# PDB_Core_v1_1_Sheet.net
KiCad netlist of a schematic drawn in Altium Designer
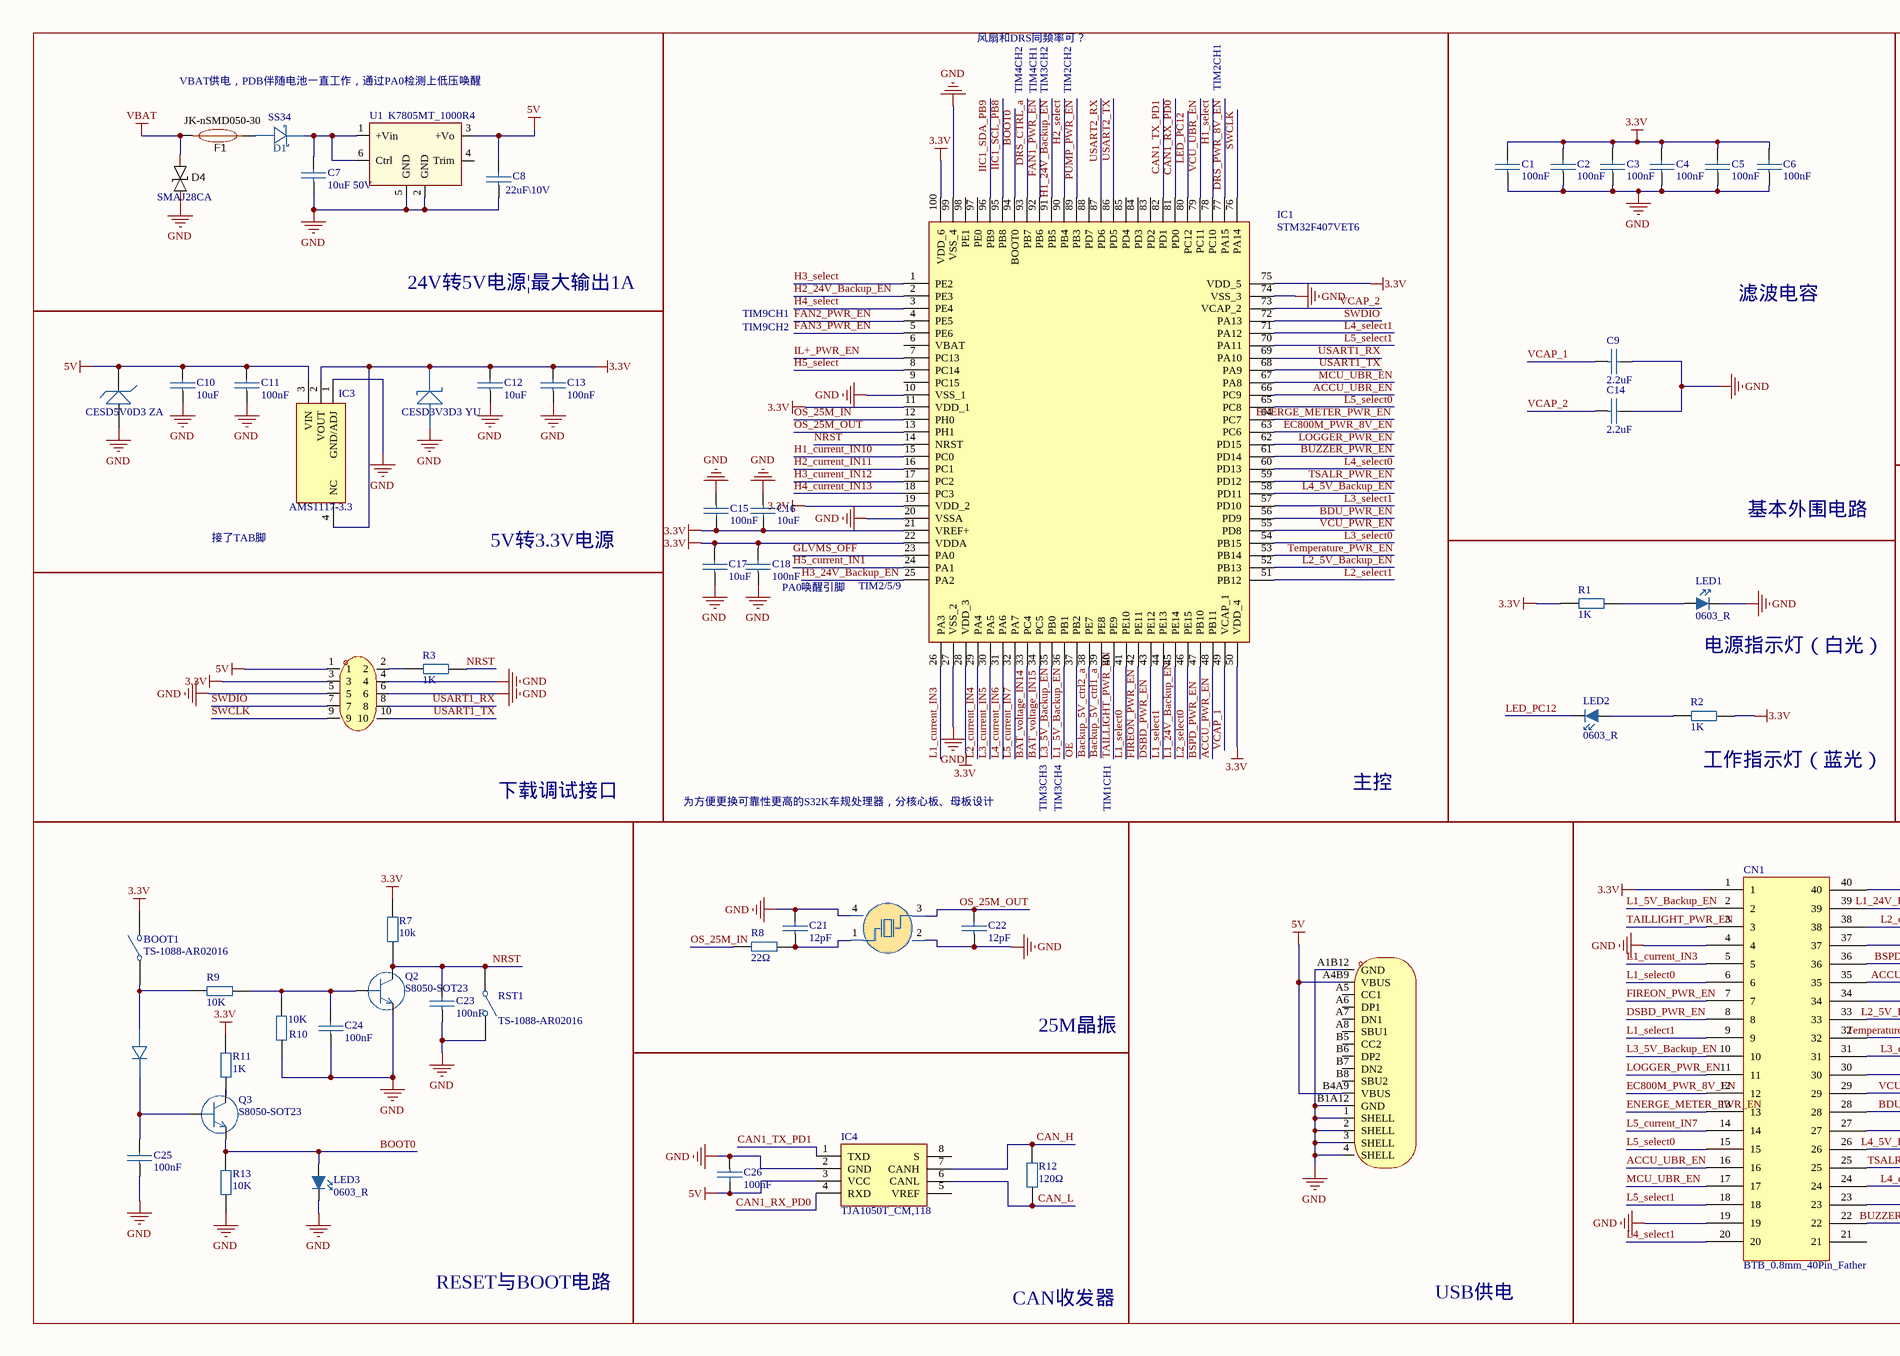
[diagram p0: PDB_Core_v1.1_Sheet.SchDoc, left]
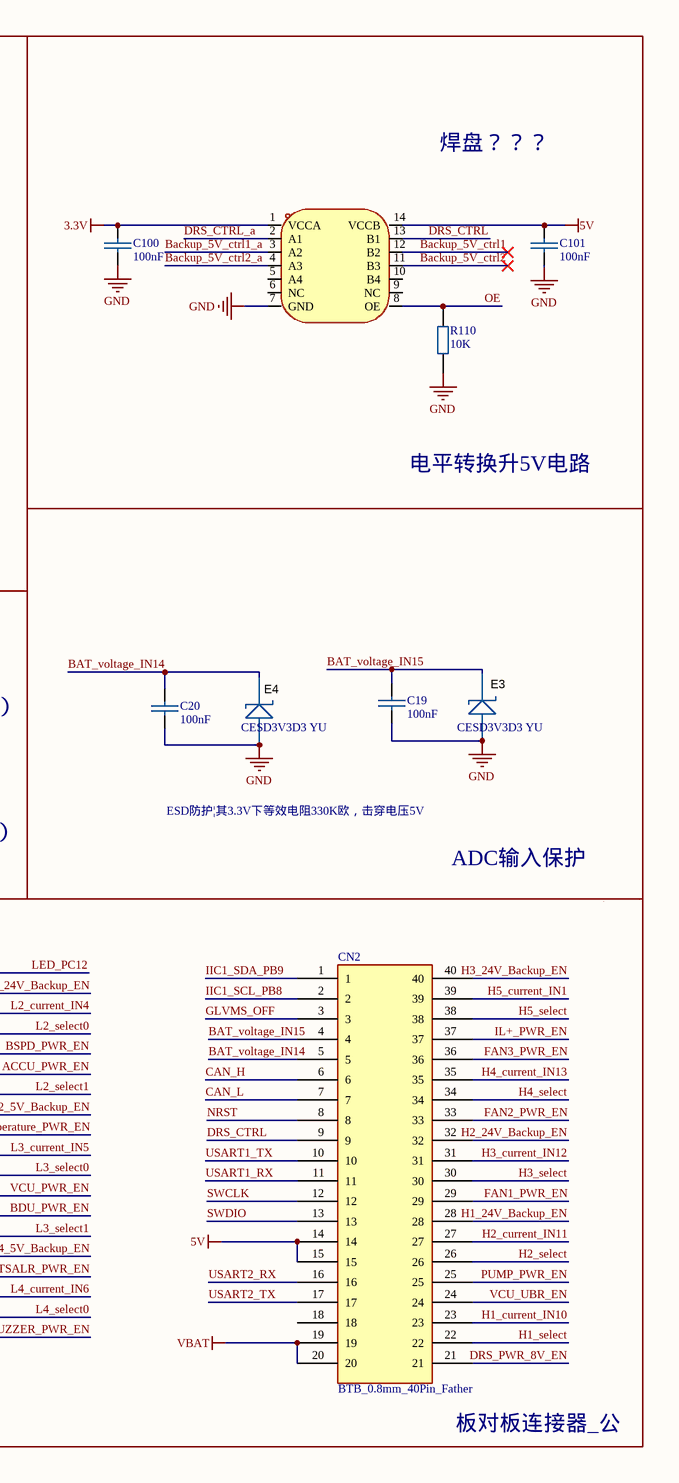
[diagram p1: PDB_Core_v1.1_Sheet.SchDoc, right]

(export (version "E")
  (design (tool "Eeschema 10.0.6"))
  (components
    (comp (ref "BOOT1")
      (value "TS-1088-AR02016")
      (footprint "SW-SMD_L3.9-W3.0-P4.45")
      (description "Switch")
      (libsource (lib "Switches") (part "TS-1088-AR02016"))
    )
    (comp (ref "C1")
      (value "100nF")
      (footprint "CAPC1608X08N__0603CAPUNPOLE")
      (description "Std MLCC Cap")
      (libsource (lib "ResistorCapacitorInductor") (part "SMD_MLCC"))
    )
    (comp (ref "C2")
      (value "100nF")
      (footprint "CAPC1608X08N__0603CAPUNPOLE")
      (description "Std MLCC Cap")
      (libsource (lib "ResistorCapacitorInductor") (part "SMD_MLCC"))
    )
    (comp (ref "C3")
      (value "100nF")
      (footprint "CAPC1608X08N__0603CAPUNPOLE")
      (description "Std MLCC Cap")
      (libsource (lib "ResistorCapacitorInductor") (part "SMD_MLCC"))
    )
    (comp (ref "C4")
      (value "100nF")
      (footprint "CAPC1608X08N__0603CAPUNPOLE")
      (description "Std MLCC Cap")
      (libsource (lib "ResistorCapacitorInductor") (part "SMD_MLCC"))
    )
    (comp (ref "C5")
      (value "100nF")
      (footprint "CAPC1608X08N__0603CAPUNPOLE")
      (description "Std MLCC Cap")
      (libsource (lib "ResistorCapacitorInductor") (part "SMD_MLCC"))
    )
    (comp (ref "C6")
      (value "100nF")
      (footprint "CAPC1608X08N__0603CAPUNPOLE")
      (description "Std MLCC Cap")
      (libsource (lib "ResistorCapacitorInductor") (part "SMD_MLCC"))
    )
    (comp (ref "C7")
      (value "10uF 50V")
      (footprint "CAPC3216X16N_1206CAPUNPOLE")
      (description "Std MLCC Cap")
      (libsource (lib "ResistorCapacitorInductor") (part "SMD_MLCC"))
    )
    (comp (ref "C8")
      (value "22u~{F}10V")
      (footprint "CAPC1608X08N__0603CAPUNPOLE")
      (description "Std MLCC Cap")
      (libsource (lib "ResistorCapacitorInductor") (part "SMD_MLCC"))
    )
    (comp (ref "C9")
      (value "2.2uF")
      (footprint "CAPC1608X08N__0603CAPUNPOLE")
      (description "Std MLCC Cap")
      (libsource (lib "ResistorCapacitorInductor") (part "SMD_MLCC"))
    )
    (comp (ref "C10")
      (value "10uF")
      (footprint "CAPC1608X08N__0603CAPUNPOLE")
      (description "Std MLCC Cap")
      (libsource (lib "ResistorCapacitorInductor") (part "SMD_MLCC"))
    )
    (comp (ref "C11")
      (value "100nF")
      (footprint "CAPC1608X08N__0603CAPUNPOLE")
      (description "Std MLCC Cap")
      (libsource (lib "ResistorCapacitorInductor") (part "SMD_MLCC"))
    )
    (comp (ref "C12")
      (value "10uF")
      (footprint "CAPC1608X08N__0603CAPUNPOLE")
      (description "Std MLCC Cap")
      (libsource (lib "ResistorCapacitorInductor") (part "SMD_MLCC"))
    )
    (comp (ref "C13")
      (value "100nF")
      (footprint "CAPC1608X08N__0603CAPUNPOLE")
      (description "Std MLCC Cap")
      (libsource (lib "ResistorCapacitorInductor") (part "SMD_MLCC"))
    )
    (comp (ref "C14")
      (value "2.2uF")
      (footprint "CAPC1608X08N__0603CAPUNPOLE")
      (description "Std MLCC Cap")
      (libsource (lib "ResistorCapacitorInductor") (part "SMD_MLCC"))
    )
    (comp (ref "C15")
      (value "100nF")
      (footprint "CAPC1608X08N__0603CAPUNPOLE")
      (description "Std MLCC Cap")
      (libsource (lib "ResistorCapacitorInductor") (part "SMD_MLCC"))
    )
    (comp (ref "C16")
      (value "10uF")
      (footprint "CAPC1608X08N__0603CAPUNPOLE")
      (description "Std MLCC Cap")
      (libsource (lib "ResistorCapacitorInductor") (part "SMD_MLCC"))
    )
    (comp (ref "C17")
      (value "10uF")
      (footprint "CAPC1608X08N__0603CAPUNPOLE")
      (description "Std MLCC Cap")
      (libsource (lib "ResistorCapacitorInductor") (part "SMD_MLCC"))
    )
    (comp (ref "C18")
      (value "100nF")
      (footprint "CAPC1608X08N__0603CAPUNPOLE")
      (description "Std MLCC Cap")
      (libsource (lib "ResistorCapacitorInductor") (part "SMD_MLCC"))
    )
    (comp (ref "C19")
      (value "100nF")
      (footprint "CAPC1608X08N__0603CAPUNPOLE")
      (description "Std MLCC Cap")
      (libsource (lib "ResistorCapacitorInductor") (part "SMD_MLCC"))
    )
    (comp (ref "C20")
      (value "100nF")
      (footprint "CAPC1608X08N__0603CAPUNPOLE")
      (description "Std MLCC Cap")
      (libsource (lib "ResistorCapacitorInductor") (part "SMD_MLCC"))
    )
    (comp (ref "C21")
      (value "12pF")
      (footprint "CAPC1608X08N__0603CAPUNPOLE")
      (description "Std MLCC Cap")
      (libsource (lib "ResistorCapacitorInductor") (part "SMD_MLCC"))
    )
    (comp (ref "C22")
      (value "12pF")
      (footprint "CAPC1608X08N__0603CAPUNPOLE")
      (description "Std MLCC Cap")
      (libsource (lib "ResistorCapacitorInductor") (part "SMD_MLCC"))
    )
    (comp (ref "C23")
      (value "100nF")
      (footprint "CAPC1608X08N__0603CAPUNPOLE")
      (description "Std MLCC Cap")
      (libsource (lib "ResistorCapacitorInductor") (part "SMD_MLCC"))
    )
    (comp (ref "C24")
      (value "100nF")
      (footprint "CAPC1608X08N__0603CAPUNPOLE")
      (description "Std MLCC Cap")
      (libsource (lib "ResistorCapacitorInductor") (part "SMD_MLCC"))
    )
    (comp (ref "C25")
      (value "100nF")
      (footprint "CAPC1608X08N__0603CAPUNPOLE")
      (description "Std MLCC Cap")
      (libsource (lib "ResistorCapacitorInductor") (part "SMD_MLCC"))
    )
    (comp (ref "C26")
      (value "100nF")
      (footprint "CAPC1608X08N__0603CAPUNPOLE")
      (description "Std MLCC Cap")
      (libsource (lib "ResistorCapacitorInductor") (part "SMD_MLCC"))
    )
    (comp (ref "C100")
      (value "100nF")
      (footprint "CAPC1608X08N__0603CAPUNPOLE")
      (description "Std MLCC Cap")
      (libsource (lib "ResistorCapacitorInductor") (part "SMD_MLCC"))
    )
    (comp (ref "C101")
      (value "100nF")
      (footprint "CAPC1608X08N__0603CAPUNPOLE")
      (description "Std MLCC Cap")
      (libsource (lib "ResistorCapacitorInductor") (part "SMD_MLCC"))
    )
    (comp (ref "CN1")
      (value "BTB_0.8mm_40Pin_Father")
      (footprint "BTB_0.8mm_40PIN_F")
      (libsource (lib "Connector") (part "BTB_0.8mm_40Pin_Father"))
    )
    (comp (ref "CN2")
      (value "BTB_0.8mm_40Pin_Father")
      (footprint "BTB_0.8mm_40PIN_F")
      (libsource (lib "Connector") (part "BTB_0.8mm_40Pin_Father"))
    )
    (comp (ref "D1")
      (value "SS34")
      (footprint "SMA_L4.3-W2.6-LS5.2-RD")
      (description "二极管配置:独立式;直流反向耐压(Vr):40V;平均整流电流(Io):3A;正向压降(Vf):550mV@3A; C8678")
      (fields (field (name "MANUFACTURER") "MDD"))
      (libsource (lib "Diodes") (part "SS34_C8678"))
    )
    (comp (ref "D3")
      (value "1N4148WS_C2128")
      (footprint "SOD-323_L1.8-W1.3-LS2.5-RD")
      (fields (field (name "MANUFACTURER") "CJ(江苏长电/长晶)") (field (name "MANUFACTURER PART") "1N4148WS"))
      (libsource (lib "Diodes") (part "1N4148WS_C2128"))
    )
    (comp (ref "D4")
      (value "SMAJ28CA")
      (footprint "SMA_L4.3-W2.5-LS5.0-BI")
      (description "C353457")
      (fields (field (name "MANUFACTURER") "晶导微电子"))
      (libsource (lib "Diodes") (part "SMAJ28CA_C353457"))
    )
    (comp (ref "E1")
      (value "CESD5V0D3 ZA")
      (footprint "SOD-323_L1.8-W1.3-LS2.5-RD")
      (fields (field (name "MANUFACTURER") "CJ(江苏长电/长晶)"))
      (libsource (lib "Diodes") (part "CESD5V0D3 ZA"))
    )
    (comp (ref "E2")
      (value "CESD3V3D3 YU")
      (footprint "SOD-323_L1.8-W1.3-LS2.5-RD")
      (description "极性:单向;反向截止电压(Vrwm):3.3V;击穿电压(VBR):5V;钳位电压(Vc)@Ipp:13V;")
      (fields (field (name "MANUFACTURER") "CJ(江苏长电/长晶)"))
      (libsource (lib "Diodes") (part "CESD3V3D3 YU"))
    )
    (comp (ref "E3")
      (value "CESD3V3D3 YU")
      (footprint "SOD-323_L1.8-W1.3-LS2.5-RD")
      (description "极性:单向;反向截止电压(Vrwm):3.3V;击穿电压(VBR):5V;钳位电压(Vc)@Ipp:13V;")
      (fields (field (name "MANUFACTURER") "CJ(江苏长电/长晶)"))
      (libsource (lib "Diodes") (part "CESD3V3D3 YU"))
    )
    (comp (ref "E4")
      (value "CESD3V3D3 YU")
      (footprint "SOD-323_L1.8-W1.3-LS2.5-RD")
      (description "极性:单向;反向截止电压(Vrwm):3.3V;击穿电压(VBR):5V;钳位电压(Vc)@Ipp:13V;")
      (fields (field (name "MANUFACTURER") "CJ(江苏长电/长晶)"))
      (libsource (lib "Diodes") (part "CESD3V3D3 YU"))
    )
    (comp (ref "F1")
      (value "JK-nSMD050-30")
      (footprint "F1206")
      (description "C720075")
      (fields (field (name "MANUFACTURER") "JK(金科)"))
      (libsource (lib "Fuse") (part "JK-nSMD050-30"))
    )
    (comp (ref "IC1")
      (value "STM32F407VET6")
      (footprint "QFP50P1600X1600X160-100N")
      (description "Integrated Circuit")
      (fields (field (name "MOUSER PART NUMBER") "511-STM32F407VET6"))
      (libsource (lib "*") (part "STM32F407VET6"))
    )
    (comp (ref "IC3")
      (value "AMS1117-3.3")
      (footprint "SOT229P700X180-4N")
      (description "Integrated Circuit")
      (libsource (lib "*") (part "AMS1117-3.3"))
    )
    (comp (ref "IC4")
      (value "TJA1050T_CM,118")
      (footprint "SOIC127P600X175-8N")
      (description "Integrated Circuit")
      (fields
        (field (name "MANUFACTURER_PART_NUMBER") "TJA1050T/CM,118")
        (field (name "MOUSER PART NUMBER") "771-TJA1050T/CM118")
      )
      (libsource (lib "*") (part "TJA1050T_CM,118"))
    )
    (comp (ref "LED1")
      (value "0603_R")
      (footprint "LED0603-RD_RED")
      (description "Light Emitting Diode")
      (libsource (lib "Diodes") (part "LED"))
    )
    (comp (ref "LED2")
      (value "0603_R")
      (footprint "LED0603-RD_RED")
      (description "Light Emitting Diode")
      (libsource (lib "Diodes") (part "LED"))
    )
    (comp (ref "LED3")
      (value "0603_R")
      (footprint "LED0603-RD_RED")
      (description "Light Emitting Diode")
      (libsource (lib "Diodes") (part "LED"))
    )
    (comp (ref "Q2")
      (value "S8050-SOT23")
      (footprint "SOT95P245X110-3N")
      (description "Jellybeam NPN")
      (libsource (lib "Transistor") (part "S8050"))
    )
    (comp (ref "Q3")
      (value "S8050-SOT23")
      (footprint "SOT95P245X110-3N")
      (description "Jellybeam NPN")
      (libsource (lib "Transistor") (part "S8050"))
    )
    (comp (ref "R1")
      (value "1K")
      (footprint "RESC1608X04N_0603RES")
      (description "Std Resistor")
      (libsource (lib "ResistorCapacitorInductor") (part "SMD_Resistor"))
    )
    (comp (ref "R2")
      (value "1K")
      (footprint "RESC1608X04N_0603RES")
      (description "Std Resistor")
      (libsource (lib "ResistorCapacitorInductor") (part "SMD_Resistor"))
    )
    (comp (ref "R3")
      (value "1K")
      (footprint "RESC3116X06N__1206RES")
      (description "Std Resistor")
      (libsource (lib "ResistorCapacitorInductor") (part "SMD_Resistor"))
    )
    (comp (ref "R7")
      (value "10k")
      (footprint "RESC1608X04N_0603RES")
      (description "Std Resistor")
      (libsource (lib "ResistorCapacitorInductor") (part "SMD_Resistor"))
    )
    (comp (ref "R8")
      (value "22Ω")
      (footprint "RESC1608X04N_0603RES")
      (description "Std Resistor")
      (libsource (lib "ResistorCapacitorInductor") (part "SMD_Resistor"))
    )
    (comp (ref "R9")
      (value "10K")
      (footprint "RESC1608X04N_0603RES")
      (description "Std Resistor")
      (libsource (lib "ResistorCapacitorInductor") (part "SMD_Resistor"))
    )
    (comp (ref "R10")
      (value "10K")
      (footprint "RESC1608X04N_0603RES")
      (description "Std Resistor")
      (libsource (lib "ResistorCapacitorInductor") (part "SMD_Resistor"))
    )
    (comp (ref "R11")
      (value "1K")
      (footprint "RESC1608X04N_0603RES")
      (description "Std Resistor")
      (libsource (lib "ResistorCapacitorInductor") (part "SMD_Resistor"))
    )
    (comp (ref "R12")
      (value "120Ω")
      (footprint "RESC1608X04N_0603RES")
      (description "Std Resistor")
      (libsource (lib "ResistorCapacitorInductor") (part "SMD_Resistor"))
    )
    (comp (ref "R13")
      (value "10K")
      (footprint "RESC1608X04N_0603RES")
      (description "Std Resistor")
      (libsource (lib "ResistorCapacitorInductor") (part "SMD_Resistor"))
    )
    (comp (ref "R110")
      (value "10K")
      (footprint "RESC1608X04N_0603RES")
      (description "Std Resistor")
      (libsource (lib "ResistorCapacitorInductor") (part "SMD_Resistor"))
    )
    (comp (ref "RST1")
      (value "TS-1088-AR02016")
      (footprint "SW-SMD_L3.9-W3.0-P4.45")
      (description "Switch")
      (libsource (lib "Switches") (part "TS-1088-AR02016"))
    )
    (comp (ref "U1")
      (value "K7805MT_1000R4")
      (footprint "K7805MT_500R4")
      (libsource (lib "DCDC_Converter") (part "K78052MT_1000R4"))
    )
    (comp (ref "U2")
      (value "ZX-PZ2.54-2-5PZZ")
      (footprint "HDR-TH_10P-P2.54-V-M-R2-C5-S2.54")
      (fields (field (name "MANUFACTURER") "Megastar(兆星)"))
      (libsource (lib "Connector") (part "ZX-PZ2.54-2-5PZZ"))
    )
    (comp (ref "U3")
      (value "TXS0104EPWR")
      (footprint "TSSOP-14_L5.0-W4.4-P0.65-LS6.4-BL")
      (description "C44955 电平转换芯片")
      (fields (field (name "MANUFACTURER") "TI(德州仪器)"))
      (libsource (lib "GateDrivers") (part "TXS0104EPWR"))
    )
    (comp (ref "USB1")
      (value "TYPE-C16PIN")
      (footprint "USB-C-SMD_TYPE-C16PIN")
      (description "C393939")
      (fields (field (name "MANUFACTURER") "SHOU HAN(首韩)"))
      (libsource (lib "Connector") (part "TYPE-C16PIN"))
    )
    (comp (ref "X1")
      (value "X322525MOB4SI")
      (footprint "OSC-SMD_4P-L3.2-W2.5-BL")
      (description "频率:25MHz;频率公差:±10ppm;负载电容:12pF;")
      (fields (field (name "MANUFACTURER") "YXC(扬兴晶振)"))
      (libsource (lib "Crystals") (part "X322525MOB4SI"))
    )
  )
  (nets
    (net (code "1") (name "/ACCU_PWR_EN") (class "Default")
      (node (ref "CN1") (pin "35") (pinfunction "35_35") (pintype "passive"))
      (node (ref "IC1") (pin "48") (pinfunction "PB11_48") (pintype "passive"))
    )
    (net (code "2") (name "/ACCU_UBR_EN") (class "Default")
      (node (ref "CN1") (pin "16") (pinfunction "16_16") (pintype "passive"))
      (node (ref "IC1") (pin "66") (pinfunction "PC9_66") (pintype "passive"))
    )
    (net (code "3") (name "/BAT_voltage_IN14") (class "Default")
      (node (ref "C20") (pin "2") (pintype "passive"))
      (node (ref "CN2") (pin "5") (pinfunction "5_5") (pintype "passive"))
      (node (ref "E4") (pin "1") (pinfunction "1_1") (pintype "passive"))
      (node (ref "IC1") (pin "33") (pinfunction "PC4_33") (pintype "passive"))
    )
    (net (code "4") (name "/BAT_voltage_IN15") (class "Default")
      (node (ref "C19") (pin "2") (pintype "passive"))
      (node (ref "CN2") (pin "4") (pinfunction "4_4") (pintype "passive"))
      (node (ref "E3") (pin "1") (pinfunction "1_1") (pintype "passive"))
      (node (ref "IC1") (pin "34") (pinfunction "PC5_34") (pintype "passive"))
    )
    (net (code "5") (name "/BDU_PWR_EN") (class "Default")
      (node (ref "CN1") (pin "28") (pinfunction "28_28") (pintype "passive"))
      (node (ref "IC1") (pin "56") (pinfunction "PD9_56") (pintype "passive"))
    )
    (net (code "6") (name "/BOOT0") (class "Default")
      (node (ref "IC1") (pin "94") (pinfunction "BOOT0_94") (pintype "passive"))
      (node (ref "LED3") (pin "2") (pintype "passive"))
      (node (ref "Q3") (pin "2") (pinfunction "Emitter_2") (pintype "passive"))
      (node (ref "R13") (pin "2") (pintype "passive"))
    )
    (net (code "7") (name "/BSPD_PWR_EN") (class "Default")
      (node (ref "CN1") (pin "36") (pinfunction "36_36") (pintype "passive"))
      (node (ref "IC1") (pin "47") (pinfunction "PB10_47") (pintype "passive"))
    )
    (net (code "8") (name "/BUZZER_PWR_EN") (class "Default")
      (node (ref "CN1") (pin "22") (pinfunction "22_22") (pintype "passive"))
      (node (ref "IC1") (pin "61") (pinfunction "PD14_61") (pintype "passive"))
    )
    (net (code "9") (name "/Backup_5V_ctrl1") (class "Default")
      (node (ref "U3") (pin "12") (pinfunction "B2_12") (pintype "passive+no_connect"))
    )
    (net (code "10") (name "/Backup_5V_ctrl1_a") (class "Default")
      (node (ref "IC1") (pin "39") (pinfunction "PE8_39") (pintype "passive"))
      (node (ref "U3") (pin "3") (pinfunction "A2_3") (pintype "passive"))
    )
    (net (code "11") (name "/Backup_5V_ctrl2") (class "Default")
      (node (ref "U3") (pin "11") (pinfunction "B3_11") (pintype "passive+no_connect"))
    )
    (net (code "12") (name "/Backup_5V_ctrl2_a") (class "Default")
      (node (ref "IC1") (pin "38") (pinfunction "PE7_38") (pintype "passive"))
      (node (ref "U3") (pin "4") (pinfunction "A3_4") (pintype "passive"))
    )
    (net (code "13") (name "/CAN1_RX_PD0") (class "Default")
      (node (ref "IC1") (pin "81") (pinfunction "PD0_81") (pintype "passive"))
      (node (ref "IC4") (pin "4") (pinfunction "RXD_4") (pintype "passive"))
    )
    (net (code "14") (name "/CAN1_TX_PD1") (class "Default")
      (node (ref "IC1") (pin "82") (pinfunction "PD1_82") (pintype "passive"))
      (node (ref "IC4") (pin "1") (pinfunction "TXD_1") (pintype "passive"))
    )
    (net (code "15") (name "/CAN_H") (class "Default")
      (node (ref "CN2") (pin "6") (pinfunction "6_6") (pintype "passive"))
      (node (ref "IC4") (pin "7") (pinfunction "CANH_7") (pintype "passive"))
      (node (ref "R12") (pin "2") (pintype "passive"))
    )
    (net (code "16") (name "/CAN_L") (class "Default")
      (node (ref "CN2") (pin "7") (pinfunction "7_7") (pintype "passive"))
      (node (ref "IC4") (pin "6") (pinfunction "CANL_6") (pintype "passive"))
      (node (ref "R12") (pin "1") (pintype "passive"))
    )
    (net (code "17") (name "/DRS_CTRL") (class "Default")
      (node (ref "CN2") (pin "9") (pinfunction "9_9") (pintype "passive"))
      (node (ref "U3") (pin "13") (pinfunction "B1_13") (pintype "passive"))
    )
    (net (code "18") (name "/DRS_CTRL_a") (class "Default")
      (node (ref "IC1") (pin "93") (pinfunction "PB7_93") (pintype "passive"))
      (node (ref "U3") (pin "2") (pinfunction "A1_2") (pintype "passive"))
    )
    (net (code "19") (name "/DRS_PWR_8V_EN") (class "Default")
      (node (ref "CN2") (pin "21") (pinfunction "21_21") (pintype "passive"))
      (node (ref "IC1") (pin "77") (pinfunction "PA15_77") (pintype "passive"))
    )
    (net (code "20") (name "/DSBD_PWR_EN") (class "Default")
      (node (ref "CN1") (pin "8") (pinfunction "8_8") (pintype "passive"))
      (node (ref "IC1") (pin "43") (pinfunction "PE12_43") (pintype "passive"))
    )
    (net (code "21") (name "/EC800M_PWR_8V_EN") (class "Default")
      (node (ref "CN1") (pin "12") (pinfunction "12_12") (pintype "passive"))
      (node (ref "IC1") (pin "63") (pinfunction "PC6_63") (pintype "passive"))
    )
    (net (code "22") (name "/ENERGE_METER_PWR_EN") (class "Default")
      (node (ref "CN1") (pin "13") (pinfunction "13_13") (pintype "passive"))
      (node (ref "IC1") (pin "64") (pinfunction "PC7_64") (pintype "passive"))
    )
    (net (code "23") (name "/FAN1_PWR_EN") (class "Default")
      (node (ref "CN2") (pin "29") (pinfunction "29_29") (pintype "passive"))
      (node (ref "IC1") (pin "92") (pinfunction "PB6_92") (pintype "passive"))
    )
    (net (code "24") (name "/FAN2_PWR_EN") (class "Default")
      (node (ref "CN2") (pin "33") (pinfunction "33_33") (pintype "passive"))
      (node (ref "IC1") (pin "4") (pinfunction "PE5_4") (pintype "passive"))
    )
    (net (code "25") (name "/FAN3_PWR_EN") (class "Default")
      (node (ref "CN2") (pin "36") (pinfunction "36_36") (pintype "passive"))
      (node (ref "IC1") (pin "5") (pinfunction "PE6_5") (pintype "passive"))
    )
    (net (code "26") (name "/FIREON_PWR_EN") (class "Default")
      (node (ref "CN1") (pin "7") (pinfunction "7_7") (pintype "passive"))
      (node (ref "IC1") (pin "42") (pinfunction "PE11_42") (pintype "passive"))
    )
    (net (code "27") (name "/GLVMS_OFF") (class "Default")
      (node (ref "CN2") (pin "3") (pinfunction "3_3") (pintype "passive"))
      (node (ref "IC1") (pin "23") (pinfunction "PA0_23") (pintype "passive"))
    )
    (net (code "28") (name "/H1_24V_Backup_EN") (class "Default")
      (node (ref "CN2") (pin "28") (pinfunction "28_28") (pintype "passive"))
      (node (ref "IC1") (pin "91") (pinfunction "PB5_91") (pintype "passive"))
    )
    (net (code "29") (name "/H1_current_IN10") (class "Default")
      (node (ref "CN2") (pin "23") (pinfunction "23_23") (pintype "passive"))
      (node (ref "IC1") (pin "15") (pinfunction "PC0_15") (pintype "passive"))
    )
    (net (code "30") (name "/H1_select") (class "Default")
      (node (ref "CN2") (pin "22") (pinfunction "22_22") (pintype "passive"))
      (node (ref "IC1") (pin "78") (pinfunction "PC10_78") (pintype "passive"))
    )
    (net (code "31") (name "/H2_24V_Backup_EN") (class "Default")
      (node (ref "CN2") (pin "32") (pinfunction "32_32") (pintype "passive"))
      (node (ref "IC1") (pin "2") (pinfunction "PE3_2") (pintype "passive"))
    )
    (net (code "32") (name "/H2_current_IN11") (class "Default")
      (node (ref "CN2") (pin "27") (pinfunction "27_27") (pintype "passive"))
      (node (ref "IC1") (pin "16") (pinfunction "PC1_16") (pintype "passive"))
    )
    (net (code "33") (name "/H2_select") (class "Default")
      (node (ref "CN2") (pin "26") (pinfunction "26_26") (pintype "passive"))
      (node (ref "IC1") (pin "90") (pinfunction "PB4_90") (pintype "passive"))
    )
    (net (code "34") (name "/H3_24V_Backup_EN") (class "Default")
      (node (ref "CN2") (pin "40") (pinfunction "40_40") (pintype "passive"))
      (node (ref "IC1") (pin "25") (pinfunction "PA2_25") (pintype "passive"))
    )
    (net (code "35") (name "/H3_current_IN12") (class "Default")
      (node (ref "CN2") (pin "31") (pinfunction "31_31") (pintype "passive"))
      (node (ref "IC1") (pin "17") (pinfunction "PC2_17") (pintype "passive"))
    )
    (net (code "36") (name "/H3_select") (class "Default")
      (node (ref "CN2") (pin "30") (pinfunction "30_30") (pintype "passive"))
      (node (ref "IC1") (pin "1") (pinfunction "PE2_1") (pintype "passive"))
    )
    (net (code "37") (name "/H4_current_IN13") (class "Default")
      (node (ref "CN2") (pin "35") (pinfunction "35_35") (pintype "passive"))
      (node (ref "IC1") (pin "18") (pinfunction "PC3_18") (pintype "passive"))
    )
    (net (code "38") (name "/H4_select") (class "Default")
      (node (ref "CN2") (pin "34") (pinfunction "34_34") (pintype "passive"))
      (node (ref "IC1") (pin "3") (pinfunction "PE4_3") (pintype "passive"))
    )
    (net (code "39") (name "/H5_current_IN1") (class "Default")
      (node (ref "CN2") (pin "39") (pinfunction "39_39") (pintype "passive"))
      (node (ref "IC1") (pin "24") (pinfunction "PA1_24") (pintype "passive"))
    )
    (net (code "40") (name "/H5_select") (class "Default")
      (node (ref "CN2") (pin "38") (pinfunction "38_38") (pintype "passive"))
      (node (ref "IC1") (pin "8") (pinfunction "PC14_8") (pintype "passive"))
    )
    (net (code "41") (name "/IIC1_SCL_PB8") (class "Default")
      (node (ref "CN2") (pin "2") (pinfunction "2_2") (pintype "passive"))
      (node (ref "IC1") (pin "95") (pinfunction "PB8_95") (pintype "passive"))
    )
    (net (code "42") (name "/IIC1_SDA_PB9") (class "Default")
      (node (ref "CN2") (pin "1") (pinfunction "1_1") (pintype "passive"))
      (node (ref "IC1") (pin "96") (pinfunction "PB9_96") (pintype "passive"))
    )
    (net (code "43") (name "/IL+_PWR_EN") (class "Default")
      (node (ref "CN2") (pin "37") (pinfunction "37_37") (pintype "passive"))
      (node (ref "IC1") (pin "7") (pinfunction "PC13_7") (pintype "passive"))
    )
    (net (code "44") (name "/L1_5V_Backup_EN") (class "Default")
      (node (ref "CN1") (pin "2") (pinfunction "2_2") (pintype "passive"))
      (node (ref "IC1") (pin "36") (pinfunction "PB1_36") (pintype "passive"))
    )
    (net (code "45") (name "/L1_24V_Backup_EN") (class "Default")
      (node (ref "CN1") (pin "39") (pinfunction "39_39") (pintype "passive"))
      (node (ref "IC1") (pin "45") (pinfunction "PE14_45") (pintype "passive"))
    )
    (net (code "46") (name "/L1_current_IN3") (class "Default")
      (node (ref "CN1") (pin "5") (pinfunction "5_5") (pintype "passive"))
      (node (ref "IC1") (pin "26") (pinfunction "PA3_26") (pintype "passive"))
    )
    (net (code "47") (name "/L1_select0") (class "Default")
      (node (ref "CN1") (pin "6") (pinfunction "6_6") (pintype "passive"))
      (node (ref "IC1") (pin "41") (pinfunction "PE10_41") (pintype "passive"))
    )
    (net (code "48") (name "/L1_select1") (class "Default")
      (node (ref "CN1") (pin "9") (pinfunction "9_9") (pintype "passive"))
      (node (ref "IC1") (pin "44") (pinfunction "PE13_44") (pintype "passive"))
    )
    (net (code "49") (name "/L2_5V_Backup_EN") (class "Default")
      (node (ref "CN1") (pin "33") (pinfunction "33_33") (pintype "passive"))
      (node (ref "IC1") (pin "52") (pinfunction "PB13_52") (pintype "passive"))
    )
    (net (code "50") (name "/L2_current_IN4") (class "Default")
      (node (ref "CN1") (pin "38") (pinfunction "38_38") (pintype "passive"))
      (node (ref "IC1") (pin "29") (pinfunction "PA4_29") (pintype "passive"))
    )
    (net (code "51") (name "/L2_select0") (class "Default")
      (node (ref "CN1") (pin "37") (pinfunction "37_37") (pintype "passive"))
      (node (ref "IC1") (pin "46") (pinfunction "PE15_46") (pintype "passive"))
    )
    (net (code "52") (name "/L2_select1") (class "Default")
      (node (ref "CN1") (pin "34") (pinfunction "34_34") (pintype "passive"))
      (node (ref "IC1") (pin "51") (pinfunction "PB12_51") (pintype "passive"))
    )
    (net (code "53") (name "/L3_5V_Backup_EN") (class "Default")
      (node (ref "CN1") (pin "10") (pinfunction "10_10") (pintype "passive"))
      (node (ref "IC1") (pin "35") (pinfunction "PB0_35") (pintype "passive"))
    )
    (net (code "54") (name "/L3_current_IN5") (class "Default")
      (node (ref "CN1") (pin "31") (pinfunction "31_31") (pintype "passive"))
      (node (ref "IC1") (pin "30") (pinfunction "PA5_30") (pintype "passive"))
    )
    (net (code "55") (name "/L3_select0") (class "Default")
      (node (ref "CN1") (pin "30") (pinfunction "30_30") (pintype "passive"))
      (node (ref "IC1") (pin "54") (pinfunction "PB15_54") (pintype "passive"))
    )
    (net (code "56") (name "/L3_select1") (class "Default")
      (node (ref "CN1") (pin "27") (pinfunction "27_27") (pintype "passive"))
      (node (ref "IC1") (pin "57") (pinfunction "PD10_57") (pintype "passive"))
    )
    (net (code "57") (name "/L4_5V_Backup_EN") (class "Default")
      (node (ref "CN1") (pin "26") (pinfunction "26_26") (pintype "passive"))
      (node (ref "IC1") (pin "58") (pinfunction "PD11_58") (pintype "passive"))
    )
    (net (code "58") (name "/L4_current_IN6") (class "Default")
      (node (ref "CN1") (pin "24") (pinfunction "24_24") (pintype "passive"))
      (node (ref "IC1") (pin "31") (pinfunction "PA6_31") (pintype "passive"))
    )
    (net (code "59") (name "/L4_select0") (class "Default")
      (node (ref "CN1") (pin "23") (pinfunction "23_23") (pintype "passive"))
      (node (ref "IC1") (pin "60") (pinfunction "PD13_60") (pintype "passive"))
    )
    (net (code "60") (name "/L4_select1") (class "Default")
      (node (ref "CN1") (pin "20") (pinfunction "20_20") (pintype "passive"))
      (node (ref "IC1") (pin "71") (pinfunction "PA12_71") (pintype "passive"))
    )
    (net (code "61") (name "/L5_current_IN7") (class "Default")
      (node (ref "CN1") (pin "14") (pinfunction "14_14") (pintype "passive"))
      (node (ref "IC1") (pin "32") (pinfunction "PA7_32") (pintype "passive"))
    )
    (net (code "62") (name "/L5_select0") (class "Default")
      (node (ref "CN1") (pin "15") (pinfunction "15_15") (pintype "passive"))
      (node (ref "IC1") (pin "65") (pinfunction "PC8_65") (pintype "passive"))
    )
    (net (code "63") (name "/L5_select1") (class "Default")
      (node (ref "CN1") (pin "18") (pinfunction "18_18") (pintype "passive"))
      (node (ref "IC1") (pin "70") (pinfunction "PA11_70") (pintype "passive"))
    )
    (net (code "64") (name "/LED_PC12") (class "Default")
      (node (ref "CN1") (pin "40") (pinfunction "40_40") (pintype "passive"))
      (node (ref "IC1") (pin "80") (pinfunction "PC12_80") (pintype "passive"))
      (node (ref "LED2") (pin "1") (pintype "passive"))
    )
    (net (code "65") (name "/LOGGER_PWR_EN") (class "Default")
      (node (ref "CN1") (pin "11") (pinfunction "11_11") (pintype "passive"))
      (node (ref "IC1") (pin "62") (pinfunction "PD15_62") (pintype "passive"))
    )
    (net (code "66") (name "/MCU_UBR_EN") (class "Default")
      (node (ref "CN1") (pin "17") (pinfunction "17_17") (pintype "passive"))
      (node (ref "IC1") (pin "67") (pinfunction "PA8_67") (pintype "passive"))
    )
    (net (code "67") (name "/NRST") (class "Default")
      (node (ref "C23") (pin "2") (pintype "passive"))
      (node (ref "CN2") (pin "8") (pinfunction "8_8") (pintype "passive"))
      (node (ref "IC1") (pin "14") (pinfunction "NRST_14") (pintype "passive"))
      (node (ref "Q2") (pin "3") (pinfunction "Collector_3") (pintype "passive"))
      (node (ref "R3") (pin "2") (pintype "passive"))
      (node (ref "R7") (pin "1") (pintype "passive"))
      (node (ref "RST1") (pin "1") (pinfunction "COMMON_1") (pintype "passive"))
    )
    (net (code "68") (name "/OE") (class "Default")
      (node (ref "IC1") (pin "37") (pinfunction "PB2_37") (pintype "passive"))
      (node (ref "R110") (pin "2") (pintype "passive"))
      (node (ref "U3") (pin "8") (pinfunction "OE_8") (pintype "passive"))
    )
    (net (code "69") (name "/OS_25M_IN") (class "Default")
      (node (ref "IC1") (pin "12") (pinfunction "PH0_12") (pintype "passive"))
      (node (ref "R8") (pin "1") (pintype "passive"))
    )
    (net (code "70") (name "/OS_25M_OUT") (class "Default")
      (node (ref "C22") (pin "2") (pintype "passive"))
      (node (ref "IC1") (pin "13") (pinfunction "PH1_13") (pintype "passive"))
      (node (ref "X1") (pin "3") (pinfunction "OSC2_3") (pintype "passive"))
    )
    (net (code "71") (name "/PUMP_PWR_EN") (class "Default")
      (node (ref "CN2") (pin "25") (pinfunction "25_25") (pintype "passive"))
      (node (ref "IC1") (pin "89") (pinfunction "PB3_89") (pintype "passive"))
    )
    (net (code "72") (name "/SWCLK") (class "Default")
      (node (ref "CN2") (pin "12") (pinfunction "12_12") (pintype "passive"))
      (node (ref "IC1") (pin "76") (pinfunction "PA14_76") (pintype "passive"))
      (node (ref "U2") (pin "9") (pinfunction "9_9") (pintype "passive"))
    )
    (net (code "73") (name "/SWDIO") (class "Default")
      (node (ref "CN2") (pin "13") (pinfunction "13_13") (pintype "passive"))
      (node (ref "IC1") (pin "72") (pinfunction "PA13_72") (pintype "passive"))
      (node (ref "U2") (pin "7") (pinfunction "7_7") (pintype "passive"))
    )
    (net (code "74") (name "/TAILLIGHT_PWR_EN") (class "Default")
      (node (ref "CN1") (pin "3") (pinfunction "3_3") (pintype "passive"))
      (node (ref "IC1") (pin "40") (pinfunction "PE9_40") (pintype "passive"))
    )
    (net (code "75") (name "/TSALR_PWR_EN") (class "Default")
      (node (ref "CN1") (pin "25") (pinfunction "25_25") (pintype "passive"))
      (node (ref "IC1") (pin "59") (pinfunction "PD12_59") (pintype "passive"))
    )
    (net (code "76") (name "/Temperature_PWR_EN") (class "Default")
      (node (ref "CN1") (pin "32") (pinfunction "32_32") (pintype "passive"))
      (node (ref "IC1") (pin "53") (pinfunction "PB14_53") (pintype "passive"))
    )
    (net (code "77") (name "/USART1_RX") (class "Default")
      (node (ref "CN2") (pin "11") (pinfunction "11_11") (pintype "passive"))
      (node (ref "IC1") (pin "69") (pinfunction "PA10_69") (pintype "passive"))
      (node (ref "U2") (pin "8") (pinfunction "8_8") (pintype "passive"))
    )
    (net (code "78") (name "/USART1_TX") (class "Default")
      (node (ref "CN2") (pin "10") (pinfunction "10_10") (pintype "passive"))
      (node (ref "IC1") (pin "68") (pinfunction "PA9_68") (pintype "passive"))
      (node (ref "U2") (pin "10") (pinfunction "10_10") (pintype "passive"))
    )
    (net (code "79") (name "/USART2_RX") (class "Default")
      (node (ref "CN2") (pin "16") (pinfunction "16_16") (pintype "passive"))
      (node (ref "IC1") (pin "87") (pinfunction "PD6_87") (pintype "passive"))
    )
    (net (code "80") (name "/USART2_TX") (class "Default")
      (node (ref "CN2") (pin "17") (pinfunction "17_17") (pintype "passive"))
      (node (ref "IC1") (pin "86") (pinfunction "PD5_86") (pintype "passive"))
    )
    (net (code "81") (name "/VCAP_1") (class "Default")
      (node (ref "C9") (pin "1") (pintype "passive"))
      (node (ref "IC1") (pin "49") (pinfunction "VCAP_1_49") (pintype "passive"))
    )
    (net (code "82") (name "/VCAP_2") (class "Default")
      (node (ref "C14") (pin "1") (pintype "passive"))
      (node (ref "IC1") (pin "73") (pinfunction "VCAP_2_73") (pintype "passive"))
    )
    (net (code "83") (name "/VCU_PWR_EN") (class "Default")
      (node (ref "CN1") (pin "29") (pinfunction "29_29") (pintype "passive"))
      (node (ref "IC1") (pin "55") (pinfunction "PD8_55") (pintype "passive"))
    )
    (net (code "84") (name "/VCU_UBR_EN") (class "Default")
      (node (ref "CN2") (pin "24") (pinfunction "24_24") (pintype "passive"))
      (node (ref "IC1") (pin "79") (pinfunction "PC11_79") (pintype "passive"))
    )
    (net (code "85") (name "3.3V") (class "Default")
      (node (ref "BOOT1") (pin "2") (pinfunction "NO_2") (pintype "passive"))
      (node (ref "C1") (pin "2") (pintype "passive"))
      (node (ref "C100") (pin "2") (pintype "passive"))
      (node (ref "C12") (pin "2") (pintype "passive"))
      (node (ref "C13") (pin "2") (pintype "passive"))
      (node (ref "C15") (pin "2") (pintype "passive"))
      (node (ref "C16") (pin "2") (pintype "passive"))
      (node (ref "C17") (pin "2") (pintype "passive"))
      (node (ref "C18") (pin "2") (pintype "passive"))
      (node (ref "C2") (pin "2") (pintype "passive"))
      (node (ref "C3") (pin "2") (pintype "passive"))
      (node (ref "C4") (pin "2") (pintype "passive"))
      (node (ref "C5") (pin "2") (pintype "passive"))
      (node (ref "C6") (pin "2") (pintype "passive"))
      (node (ref "CN1") (pin "1") (pinfunction "1_1") (pintype "passive"))
      (node (ref "E2") (pin "1") (pinfunction "1_1") (pintype "passive"))
      (node (ref "IC1") (pin "100") (pinfunction "VDD_6_100") (pintype "passive"))
      (node (ref "IC1") (pin "11") (pinfunction "VDD_1_11") (pintype "passive"))
      (node (ref "IC1") (pin "19") (pinfunction "VDD_2_19") (pintype "passive"))
      (node (ref "IC1") (pin "21") (pinfunction "VREF+_21") (pintype "passive"))
      (node (ref "IC1") (pin "22") (pinfunction "VDDA_22") (pintype "passive"))
      (node (ref "IC1") (pin "28") (pinfunction "VDD_3_28") (pintype "passive"))
      (node (ref "IC1") (pin "50") (pinfunction "VDD_4_50") (pintype "passive"))
      (node (ref "IC1") (pin "75") (pinfunction "VDD_5_75") (pintype "passive"))
      (node (ref "IC3") (pin "2") (pinfunction "VOUT_2") (pintype "passive"))
      (node (ref "IC3") (pin "4") (pinfunction "NC_4") (pintype "passive"))
      (node (ref "R1") (pin "1") (pintype "passive"))
      (node (ref "R11") (pin "2") (pintype "passive"))
      (node (ref "R2") (pin "2") (pintype "passive"))
      (node (ref "R7") (pin "2") (pintype "passive"))
      (node (ref "U2") (pin "3") (pinfunction "3_3") (pintype "passive"))
      (node (ref "U3") (pin "1") (pinfunction "VCCA_1") (pintype "passive"))
    )
    (net (code "86") (name "5V") (class "Default")
      (node (ref "C10") (pin "2") (pintype "passive"))
      (node (ref "C101") (pin "2") (pintype "passive"))
      (node (ref "C11") (pin "2") (pintype "passive"))
      (node (ref "C26") (pin "2") (pintype "passive"))
      (node (ref "C8") (pin "2") (pintype "passive"))
      (node (ref "CN2") (pin "14") (pinfunction "14_14") (pintype "passive"))
      (node (ref "CN2") (pin "15") (pinfunction "15_15") (pintype "passive"))
      (node (ref "E1") (pin "1") (pinfunction "1_1") (pintype "passive"))
      (node (ref "IC3") (pin "3") (pinfunction "VIN_3") (pintype "passive"))
      (node (ref "IC4") (pin "3") (pinfunction "VCC_3") (pintype "passive"))
      (node (ref "U1") (pin "3") (pinfunction "+Vo_3") (pintype "passive"))
      (node (ref "U2") (pin "1") (pinfunction "1_1") (pintype "passive"))
      (node (ref "U3") (pin "14") (pinfunction "VCCB_14") (pintype "passive"))
      (node (ref "USB1") (pin "A4B9") (pinfunction "VBUS_A4B9") (pintype "passive"))
      (node (ref "USB1") (pin "B4A9") (pinfunction "VBUS_B4A9") (pintype "passive"))
    )
    (net (code "87") (name "GND") (class "Default")
      (node (ref "C1") (pin "1") (pintype "passive"))
      (node (ref "C10") (pin "1") (pintype "passive"))
      (node (ref "C100") (pin "1") (pintype "passive"))
      (node (ref "C101") (pin "1") (pintype "passive"))
      (node (ref "C11") (pin "1") (pintype "passive"))
      (node (ref "C12") (pin "1") (pintype "passive"))
      (node (ref "C13") (pin "1") (pintype "passive"))
      (node (ref "C14") (pin "2") (pintype "passive"))
      (node (ref "C15") (pin "1") (pintype "passive"))
      (node (ref "C16") (pin "1") (pintype "passive"))
      (node (ref "C17") (pin "1") (pintype "passive"))
      (node (ref "C18") (pin "1") (pintype "passive"))
      (node (ref "C19") (pin "1") (pintype "passive"))
      (node (ref "C2") (pin "1") (pintype "passive"))
      (node (ref "C20") (pin "1") (pintype "passive"))
      (node (ref "C21") (pin "2") (pintype "passive"))
      (node (ref "C22") (pin "1") (pintype "passive"))
      (node (ref "C23") (pin "1") (pintype "passive"))
      (node (ref "C24") (pin "1") (pintype "passive"))
      (node (ref "C25") (pin "1") (pintype "passive"))
      (node (ref "C26") (pin "1") (pintype "passive"))
      (node (ref "C3") (pin "1") (pintype "passive"))
      (node (ref "C4") (pin "1") (pintype "passive"))
      (node (ref "C5") (pin "1") (pintype "passive"))
      (node (ref "C6") (pin "1") (pintype "passive"))
      (node (ref "C7") (pin "1") (pintype "passive"))
      (node (ref "C8") (pin "1") (pintype "passive"))
      (node (ref "C9") (pin "2") (pintype "passive"))
      (node (ref "CN1") (pin "19") (pinfunction "19_19") (pintype "passive"))
      (node (ref "CN1") (pin "4") (pinfunction "4_4") (pintype "passive"))
      (node (ref "D4") (pin "1") (pinfunction "1_1") (pintype "passive"))
      (node (ref "E1") (pin "2") (pinfunction "2_2") (pintype "passive"))
      (node (ref "E2") (pin "2") (pinfunction "2_2") (pintype "passive"))
      (node (ref "E3") (pin "2") (pinfunction "2_2") (pintype "passive"))
      (node (ref "E4") (pin "2") (pinfunction "2_2") (pintype "passive"))
      (node (ref "IC1") (pin "10") (pinfunction "VSS_1_10") (pintype "passive"))
      (node (ref "IC1") (pin "20") (pinfunction "VSSA_20") (pintype "passive"))
      (node (ref "IC1") (pin "27") (pinfunction "VSS_2_27") (pintype "passive"))
      (node (ref "IC1") (pin "74") (pinfunction "VSS_3_74") (pintype "passive"))
      (node (ref "IC1") (pin "99") (pinfunction "VSS_4_99") (pintype "passive"))
      (node (ref "IC3") (pin "1") (pinfunction "GND/ADJ_1") (pintype "passive"))
      (node (ref "IC4") (pin "2") (pinfunction "GND_2") (pintype "passive"))
      (node (ref "LED1") (pin "1") (pintype "passive"))
      (node (ref "LED3") (pin "1") (pintype "passive"))
      (node (ref "Q2") (pin "2") (pinfunction "Emitter_2") (pintype "passive"))
      (node (ref "R10") (pin "1") (pintype "passive"))
      (node (ref "R110") (pin "1") (pintype "passive"))
      (node (ref "R13") (pin "1") (pintype "passive"))
      (node (ref "RST1") (pin "2") (pinfunction "NO_2") (pintype "passive"))
      (node (ref "U1") (pin "2") (pinfunction "GND_2") (pintype "passive"))
      (node (ref "U1") (pin "5") (pinfunction "GND_5") (pintype "passive"))
      (node (ref "U2") (pin "4") (pinfunction "4_4") (pintype "passive"))
      (node (ref "U2") (pin "5") (pinfunction "5_5") (pintype "passive"))
      (node (ref "U2") (pin "6") (pinfunction "6_6") (pintype "passive"))
      (node (ref "U3") (pin "7") (pinfunction "GND_7") (pintype "passive"))
      (node (ref "USB1") (pin "1") (pinfunction "SHELL_1") (pintype "passive"))
      (node (ref "USB1") (pin "2") (pinfunction "SHELL_2") (pintype "passive"))
      (node (ref "USB1") (pin "3") (pinfunction "SHELL_3") (pintype "passive"))
      (node (ref "USB1") (pin "4") (pinfunction "SHELL_4") (pintype "passive"))
      (node (ref "USB1") (pin "A1B12") (pinfunction "GND_A1B12") (pintype "passive"))
      (node (ref "USB1") (pin "B1A12") (pinfunction "GND_B1A12") (pintype "passive"))
      (node (ref "X1") (pin "2") (pinfunction "GND_2") (pintype "passive"))
      (node (ref "X1") (pin "4") (pinfunction "GND_4") (pintype "passive"))
    )
    (net (code "88") (name "Net-(BOOT1-COMMON)") (class "Default")
      (node (ref "BOOT1") (pin "1") (pinfunction "COMMON_1") (pintype "passive"))
      (node (ref "D3") (pin "2") (pinfunction "A_2") (pintype "passive"))
      (node (ref "R9") (pin "1") (pintype "passive"))
    )
    (net (code "89") (name "Net-(D1-A)") (class "Default")
      (node (ref "D1") (pin "2") (pinfunction "A_2") (pintype "passive"))
      (node (ref "F1") (pin "2") (pinfunction "2_2") (pintype "passive"))
    )
    (net (code "90") (name "Net-(D1-K)") (class "Default")
      (node (ref "C7") (pin "2") (pintype "passive"))
      (node (ref "D1") (pin "1") (pinfunction "K_1") (pintype "passive"))
      (node (ref "U1") (pin "1") (pinfunction "+Vin_1") (pintype "passive"))
      (node (ref "U1") (pin "6") (pinfunction "Ctrl_6") (pintype "passive"))
    )
    (net (code "91") (name "Net-(D3-K)") (class "Default")
      (node (ref "C25") (pin "2") (pintype "passive"))
      (node (ref "D3") (pin "1") (pinfunction "K_1") (pintype "passive"))
      (node (ref "Q3") (pin "1") (pinfunction "Base_1") (pintype "passive"))
    )
    (net (code "92") (name "Net-(LED1-Pad2)") (class "Default")
      (node (ref "LED1") (pin "2") (pintype "passive"))
      (node (ref "R1") (pin "2") (pintype "passive"))
    )
    (net (code "93") (name "Net-(LED2-Pad2)") (class "Default")
      (node (ref "LED2") (pin "2") (pintype "passive"))
      (node (ref "R2") (pin "1") (pintype "passive"))
    )
    (net (code "94") (name "Net-(Q2-Base)") (class "Default")
      (node (ref "C24") (pin "2") (pintype "passive"))
      (node (ref "Q2") (pin "1") (pinfunction "Base_1") (pintype "passive"))
      (node (ref "R10") (pin "2") (pintype "passive"))
      (node (ref "R9") (pin "2") (pintype "passive"))
    )
    (net (code "95") (name "Net-(Q3-Collector)") (class "Default")
      (node (ref "Q3") (pin "3") (pinfunction "Collector_3") (pintype "passive"))
      (node (ref "R11") (pin "1") (pintype "passive"))
    )
    (net (code "96") (name "Net-(R3-Pad1)") (class "Default")
      (node (ref "R3") (pin "1") (pintype "passive"))
      (node (ref "U2") (pin "2") (pinfunction "2_2") (pintype "passive"))
    )
    (net (code "97") (name "Net-(X1-OSC1)") (class "Default")
      (node (ref "C21") (pin "1") (pintype "passive"))
      (node (ref "R8") (pin "2") (pintype "passive"))
      (node (ref "X1") (pin "1") (pinfunction "OSC1_1") (pintype "passive"))
    )
    (net (code "98") (name "VBAT") (class "Default")
      (node (ref "CN2") (pin "19") (pinfunction "19_19") (pintype "passive"))
      (node (ref "CN2") (pin "20") (pinfunction "20_20") (pintype "passive"))
      (node (ref "D4") (pin "2") (pinfunction "2_2") (pintype "passive"))
      (node (ref "F1") (pin "1") (pinfunction "1_1") (pintype "passive"))
    )
    (net (code "99") (name "unconnected-(CN1-Pad21)") (class "Default")
      (node (ref "CN1") (pin "21") (pinfunction "21_21") (pintype "passive"))
    )
    (net (code "100") (name "unconnected-(CN2-Pad18)") (class "Default")
      (node (ref "CN2") (pin "18") (pinfunction "18_18") (pintype "passive"))
    )
    (net (code "101") (name "unconnected-(IC1-PC15-Pad9)") (class "Default")
      (node (ref "IC1") (pin "9") (pinfunction "PC15_9") (pintype "passive"))
    )
    (net (code "102") (name "unconnected-(IC1-PD2-Pad83)") (class "Default")
      (node (ref "IC1") (pin "83") (pinfunction "PD2_83") (pintype "passive"))
    )
    (net (code "103") (name "unconnected-(IC1-PD3-Pad84)") (class "Default")
      (node (ref "IC1") (pin "84") (pinfunction "PD3_84") (pintype "passive"))
    )
    (net (code "104") (name "unconnected-(IC1-PD4-Pad85)") (class "Default")
      (node (ref "IC1") (pin "85") (pinfunction "PD4_85") (pintype "passive"))
    )
    (net (code "105") (name "unconnected-(IC1-PD7-Pad88)") (class "Default")
      (node (ref "IC1") (pin "88") (pinfunction "PD7_88") (pintype "passive"))
    )
    (net (code "106") (name "unconnected-(IC1-PE0-Pad97)") (class "Default")
      (node (ref "IC1") (pin "97") (pinfunction "PE0_97") (pintype "passive"))
    )
    (net (code "107") (name "unconnected-(IC1-PE1-Pad98)") (class "Default")
      (node (ref "IC1") (pin "98") (pinfunction "PE1_98") (pintype "passive"))
    )
    (net (code "108") (name "unconnected-(IC1-VBAT-Pad6)") (class "Default")
      (node (ref "IC1") (pin "6") (pinfunction "VBAT_6") (pintype "passive"))
    )
    (net (code "109") (name "unconnected-(IC4-S-Pad8)") (class "Default")
      (node (ref "IC4") (pin "8") (pinfunction "S_8") (pintype "passive"))
    )
    (net (code "110") (name "unconnected-(IC4-VREF-Pad5)") (class "Default")
      (node (ref "IC4") (pin "5") (pinfunction "VREF_5") (pintype "passive"))
    )
    (net (code "111") (name "unconnected-(U1-Trim-Pad4)") (class "Default")
      (node (ref "U1") (pin "4") (pinfunction "Trim_4") (pintype "passive"))
    )
    (net (code "112") (name "unconnected-(U3-A4-Pad5)") (class "Default")
      (node (ref "U3") (pin "5") (pinfunction "A4_5") (pintype "passive"))
    )
    (net (code "113") (name "unconnected-(U3-B4-Pad10)") (class "Default")
      (node (ref "U3") (pin "10") (pinfunction "B4_10") (pintype "passive"))
    )
    (net (code "114") (name "unconnected-(U3-NC-Pad6)") (class "Default")
      (node (ref "U3") (pin "6") (pinfunction "NC_6") (pintype "passive"))
    )
    (net (code "115") (name "unconnected-(U3-NC-Pad9)") (class "Default")
      (node (ref "U3") (pin "9") (pinfunction "NC_9") (pintype "passive"))
    )
    (net (code "116") (name "unconnected-(USB1-CC1-PadA5)") (class "Default")
      (node (ref "USB1") (pin "A5") (pinfunction "CC1_A5") (pintype "passive"))
    )
    (net (code "117") (name "unconnected-(USB1-CC2-PadB5)") (class "Default")
      (node (ref "USB1") (pin "B5") (pinfunction "CC2_B5") (pintype "passive"))
    )
    (net (code "118") (name "unconnected-(USB1-DN1-PadA7)") (class "Default")
      (node (ref "USB1") (pin "A7") (pinfunction "DN1_A7") (pintype "passive"))
    )
    (net (code "119") (name "unconnected-(USB1-DN2-PadB7)") (class "Default")
      (node (ref "USB1") (pin "B7") (pinfunction "DN2_B7") (pintype "passive"))
    )
    (net (code "120") (name "unconnected-(USB1-DP1-PadA6)") (class "Default")
      (node (ref "USB1") (pin "A6") (pinfunction "DP1_A6") (pintype "passive"))
    )
    (net (code "121") (name "unconnected-(USB1-DP2-PadB6)") (class "Default")
      (node (ref "USB1") (pin "B6") (pinfunction "DP2_B6") (pintype "passive"))
    )
    (net (code "122") (name "unconnected-(USB1-SBU1-PadA8)") (class "Default")
      (node (ref "USB1") (pin "A8") (pinfunction "SBU1_A8") (pintype "passive"))
    )
    (net (code "123") (name "unconnected-(USB1-SBU2-PadB8)") (class "Default")
      (node (ref "USB1") (pin "B8") (pinfunction "SBU2_B8") (pintype "passive"))
    )
  )
)
